# DRIVER.net
KiCad netlist of a schematic drawn in EAGLE
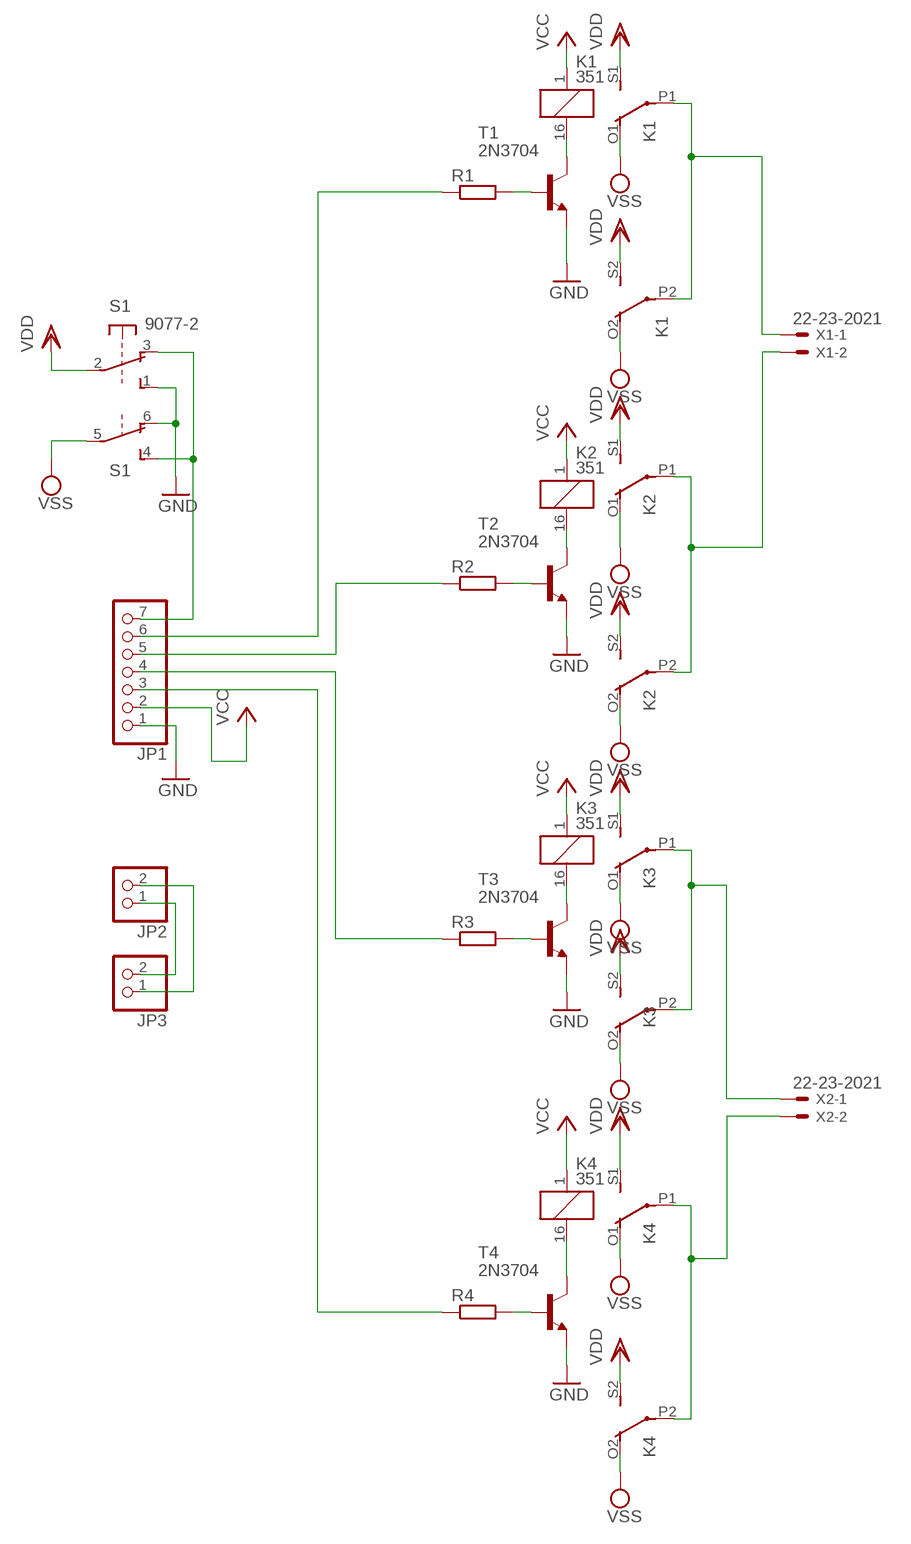
[diagram p0: schematic, sheet 1]

(export (version "E")
  (design (tool "Eeschema 10.0.6"))
  (components
    (comp (ref "JP1")
      (value "PINHD-1X7")
      (footprint "eagle-import:1X07")
      (libsource (lib "eagle-import") (part "PINHD-1X7"))
    )
    (comp (ref "JP2")
      (value "PINHD-1X2")
      (footprint "eagle-import:1X02")
      (libsource (lib "eagle-import") (part "PINHD-1X2"))
    )
    (comp (ref "JP3")
      (value "PINHD-1X2")
      (footprint "eagle-import:1X02")
      (libsource (lib "eagle-import") (part "PINHD-1X2"))
    )
    (comp (ref "K1")
      (value "351")
      (footprint "eagle-import:351")
      (libsource (lib "eagle-import") (part "351"))
    )
    (comp (ref "K2")
      (value "351")
      (footprint "eagle-import:351")
      (libsource (lib "eagle-import") (part "351"))
    )
    (comp (ref "K3")
      (value "351")
      (footprint "eagle-import:351")
      (libsource (lib "eagle-import") (part "351"))
    )
    (comp (ref "K4")
      (value "351")
      (footprint "eagle-import:351")
      (libsource (lib "eagle-import") (part "351"))
    )
    (comp (ref "R1")
      (value "R-EU_0207/7")
      (footprint "eagle-import:0207_7")
      (libsource (lib "eagle-import") (part "R-EU_0207/7"))
    )
    (comp (ref "R2")
      (value "R-EU_0207/7")
      (footprint "eagle-import:0207_7")
      (libsource (lib "eagle-import") (part "R-EU_0207/7"))
    )
    (comp (ref "R3")
      (value "R-EU_0207/7")
      (footprint "eagle-import:0207_7")
      (libsource (lib "eagle-import") (part "R-EU_0207/7"))
    )
    (comp (ref "R4")
      (value "R-EU_0207/7")
      (footprint "eagle-import:0207_7")
      (libsource (lib "eagle-import") (part "R-EU_0207/7"))
    )
    (comp (ref "S1")
      (value "9077-2")
      (footprint "eagle-import:9077-2")
      (libsource (lib "eagle-import") (part "9077-2"))
    )
    (comp (ref "T1")
      (value "2N3704")
      (footprint "eagle-import:TO92")
      (libsource (lib "eagle-import") (part "2N3704"))
    )
    (comp (ref "T2")
      (value "2N3704")
      (footprint "eagle-import:TO92")
      (libsource (lib "eagle-import") (part "2N3704"))
    )
    (comp (ref "T3")
      (value "2N3704")
      (footprint "eagle-import:TO92")
      (libsource (lib "eagle-import") (part "2N3704"))
    )
    (comp (ref "T4")
      (value "2N3704")
      (footprint "eagle-import:TO92")
      (libsource (lib "eagle-import") (part "2N3704"))
    )
    (comp (ref "X1")
      (value "22-23-2021")
      (footprint "eagle-import:22-23-2021")
      (fields (field (name "MF") "MOLEX"))
      (libsource (lib "eagle-import") (part "22-23-2021"))
    )
    (comp (ref "X2")
      (value "22-23-2021")
      (footprint "eagle-import:22-23-2021")
      (fields (field (name "MF") "MOLEX"))
      (libsource (lib "eagle-import") (part "22-23-2021"))
    )
  )
  (nets
    (net (code "1") (name "GND") (class "Default")
      (node (ref "JP1") (pin "1") (pinfunction "1_1") (pintype "passive"))
      (node (ref "S1") (pin "1") (pinfunction "S_1") (pintype "passive"))
      (node (ref "S1") (pin "6") (pinfunction "O_6") (pintype "passive"))
      (node (ref "T1") (pin "3") (pinfunction "E_3") (pintype "passive"))
      (node (ref "T2") (pin "3") (pinfunction "E_3") (pintype "passive"))
      (node (ref "T3") (pin "3") (pinfunction "E_3") (pintype "passive"))
      (node (ref "T4") (pin "3") (pinfunction "E_3") (pintype "passive"))
    )
    (net (code "2") (name "Net-(JP1-Pad3)") (class "Default")
      (node (ref "JP1") (pin "3") (pinfunction "3_3") (pintype "passive"))
      (node (ref "R4") (pin "1") (pinfunction "1_1") (pintype "passive"))
    )
    (net (code "3") (name "Net-(JP1-Pad4)") (class "Default")
      (node (ref "JP1") (pin "4") (pinfunction "4_4") (pintype "passive"))
      (node (ref "R3") (pin "1") (pinfunction "1_1") (pintype "passive"))
    )
    (net (code "4") (name "Net-(JP1-Pad5)") (class "Default")
      (node (ref "JP1") (pin "5") (pinfunction "5_5") (pintype "passive"))
      (node (ref "R2") (pin "1") (pinfunction "1_1") (pintype "passive"))
    )
    (net (code "5") (name "Net-(JP1-Pad6)") (class "Default")
      (node (ref "JP1") (pin "6") (pinfunction "6_6") (pintype "passive"))
      (node (ref "R1") (pin "1") (pinfunction "1_1") (pintype "passive"))
    )
    (net (code "6") (name "Net-(JP2-Pad1)") (class "Default")
      (node (ref "JP2") (pin "1") (pinfunction "1_1") (pintype "passive"))
      (node (ref "JP3") (pin "2") (pinfunction "2_2") (pintype "passive"))
    )
    (net (code "7") (name "Net-(JP2-Pad2)") (class "Default")
      (node (ref "JP2") (pin "2") (pinfunction "2_2") (pintype "passive"))
      (node (ref "JP3") (pin "1") (pinfunction "1_1") (pintype "passive"))
    )
    (net (code "8") (name "Net-(K1A-2)") (class "Default")
      (node (ref "K1") (pin "16") (pinfunction "2_16") (pintype "passive"))
      (node (ref "T1") (pin "2") (pinfunction "C_2") (pintype "passive"))
    )
    (net (code "9") (name "Net-(K1B-P)") (class "Default")
      (node (ref "K1") (pin "P1") (pinfunction "P_P1") (pintype "passive"))
      (node (ref "K1") (pin "P2") (pinfunction "P_P2") (pintype "passive"))
      (node (ref "X1") (pin "1") (pinfunction "S_1") (pintype "passive"))
    )
    (net (code "10") (name "Net-(K2A-2)") (class "Default")
      (node (ref "K2") (pin "16") (pinfunction "2_16") (pintype "passive"))
      (node (ref "T2") (pin "2") (pinfunction "C_2") (pintype "passive"))
    )
    (net (code "11") (name "Net-(K2B-P)") (class "Default")
      (node (ref "K2") (pin "P1") (pinfunction "P_P1") (pintype "passive"))
      (node (ref "K2") (pin "P2") (pinfunction "P_P2") (pintype "passive"))
      (node (ref "X1") (pin "2") (pinfunction "S_2") (pintype "passive"))
    )
    (net (code "12") (name "Net-(K3A-2)") (class "Default")
      (node (ref "K3") (pin "16") (pinfunction "2_16") (pintype "passive"))
      (node (ref "T3") (pin "2") (pinfunction "C_2") (pintype "passive"))
    )
    (net (code "13") (name "Net-(K3B-P)") (class "Default")
      (node (ref "K3") (pin "P1") (pinfunction "P_P1") (pintype "passive"))
      (node (ref "K3") (pin "P2") (pinfunction "P_P2") (pintype "passive"))
      (node (ref "X2") (pin "1") (pinfunction "S_1") (pintype "passive"))
    )
    (net (code "14") (name "Net-(K4A-2)") (class "Default")
      (node (ref "K4") (pin "16") (pinfunction "2_16") (pintype "passive"))
      (node (ref "T4") (pin "2") (pinfunction "C_2") (pintype "passive"))
    )
    (net (code "15") (name "Net-(K4B-P)") (class "Default")
      (node (ref "K4") (pin "P1") (pinfunction "P_P1") (pintype "passive"))
      (node (ref "K4") (pin "P2") (pinfunction "P_P2") (pintype "passive"))
      (node (ref "X2") (pin "2") (pinfunction "S_2") (pintype "passive"))
    )
    (net (code "16") (name "Net-(S1A-O)") (class "Default")
      (node (ref "JP1") (pin "7") (pinfunction "7_7") (pintype "passive"))
      (node (ref "S1") (pin "3") (pinfunction "O_3") (pintype "passive"))
      (node (ref "S1") (pin "4") (pinfunction "S_4") (pintype "passive"))
    )
    (net (code "17") (name "Net-(T1-B)") (class "Default")
      (node (ref "R1") (pin "2") (pinfunction "2_2") (pintype "passive"))
      (node (ref "T1") (pin "1") (pinfunction "B_1") (pintype "passive"))
    )
    (net (code "18") (name "Net-(T2-B)") (class "Default")
      (node (ref "R2") (pin "2") (pinfunction "2_2") (pintype "passive"))
      (node (ref "T2") (pin "1") (pinfunction "B_1") (pintype "passive"))
    )
    (net (code "19") (name "Net-(T3-B)") (class "Default")
      (node (ref "R3") (pin "2") (pinfunction "2_2") (pintype "passive"))
      (node (ref "T3") (pin "1") (pinfunction "B_1") (pintype "passive"))
    )
    (net (code "20") (name "Net-(T4-B)") (class "Default")
      (node (ref "R4") (pin "2") (pinfunction "2_2") (pintype "passive"))
      (node (ref "T4") (pin "1") (pinfunction "B_1") (pintype "passive"))
    )
    (net (code "21") (name "VCC") (class "Default")
      (node (ref "JP1") (pin "2") (pinfunction "2_2") (pintype "passive"))
      (node (ref "K1") (pin "1") (pinfunction "1_1") (pintype "passive"))
      (node (ref "K2") (pin "1") (pinfunction "1_1") (pintype "passive"))
      (node (ref "K3") (pin "1") (pinfunction "1_1") (pintype "passive"))
      (node (ref "K4") (pin "1") (pinfunction "1_1") (pintype "passive"))
    )
    (net (code "22") (name "VDD") (class "Default")
      (node (ref "K1") (pin "S1") (pinfunction "S_S1") (pintype "passive"))
      (node (ref "K1") (pin "S2") (pinfunction "S_S2") (pintype "passive"))
      (node (ref "K2") (pin "S1") (pinfunction "S_S1") (pintype "passive"))
      (node (ref "K2") (pin "S2") (pinfunction "S_S2") (pintype "passive"))
      (node (ref "K3") (pin "S1") (pinfunction "S_S1") (pintype "passive"))
      (node (ref "K3") (pin "S2") (pinfunction "S_S2") (pintype "passive"))
      (node (ref "K4") (pin "S1") (pinfunction "S_S1") (pintype "passive"))
      (node (ref "K4") (pin "S2") (pinfunction "S_S2") (pintype "passive"))
      (node (ref "S1") (pin "2") (pinfunction "P_2") (pintype "passive"))
    )
    (net (code "23") (name "VSS") (class "Default")
      (node (ref "K1") (pin "O1") (pinfunction "O_O1") (pintype "passive"))
      (node (ref "K1") (pin "O2") (pinfunction "O_O2") (pintype "passive"))
      (node (ref "K2") (pin "O1") (pinfunction "O_O1") (pintype "passive"))
      (node (ref "K2") (pin "O2") (pinfunction "O_O2") (pintype "passive"))
      (node (ref "K3") (pin "O1") (pinfunction "O_O1") (pintype "passive"))
      (node (ref "K3") (pin "O2") (pinfunction "O_O2") (pintype "passive"))
      (node (ref "K4") (pin "O1") (pinfunction "O_O1") (pintype "passive"))
      (node (ref "K4") (pin "O2") (pinfunction "O_O2") (pintype "passive"))
      (node (ref "S1") (pin "5") (pinfunction "P_5") (pintype "passive"))
    )
  )
)
